# Sheet1.net
KiCad netlist of a schematic drawn in Altium Designer
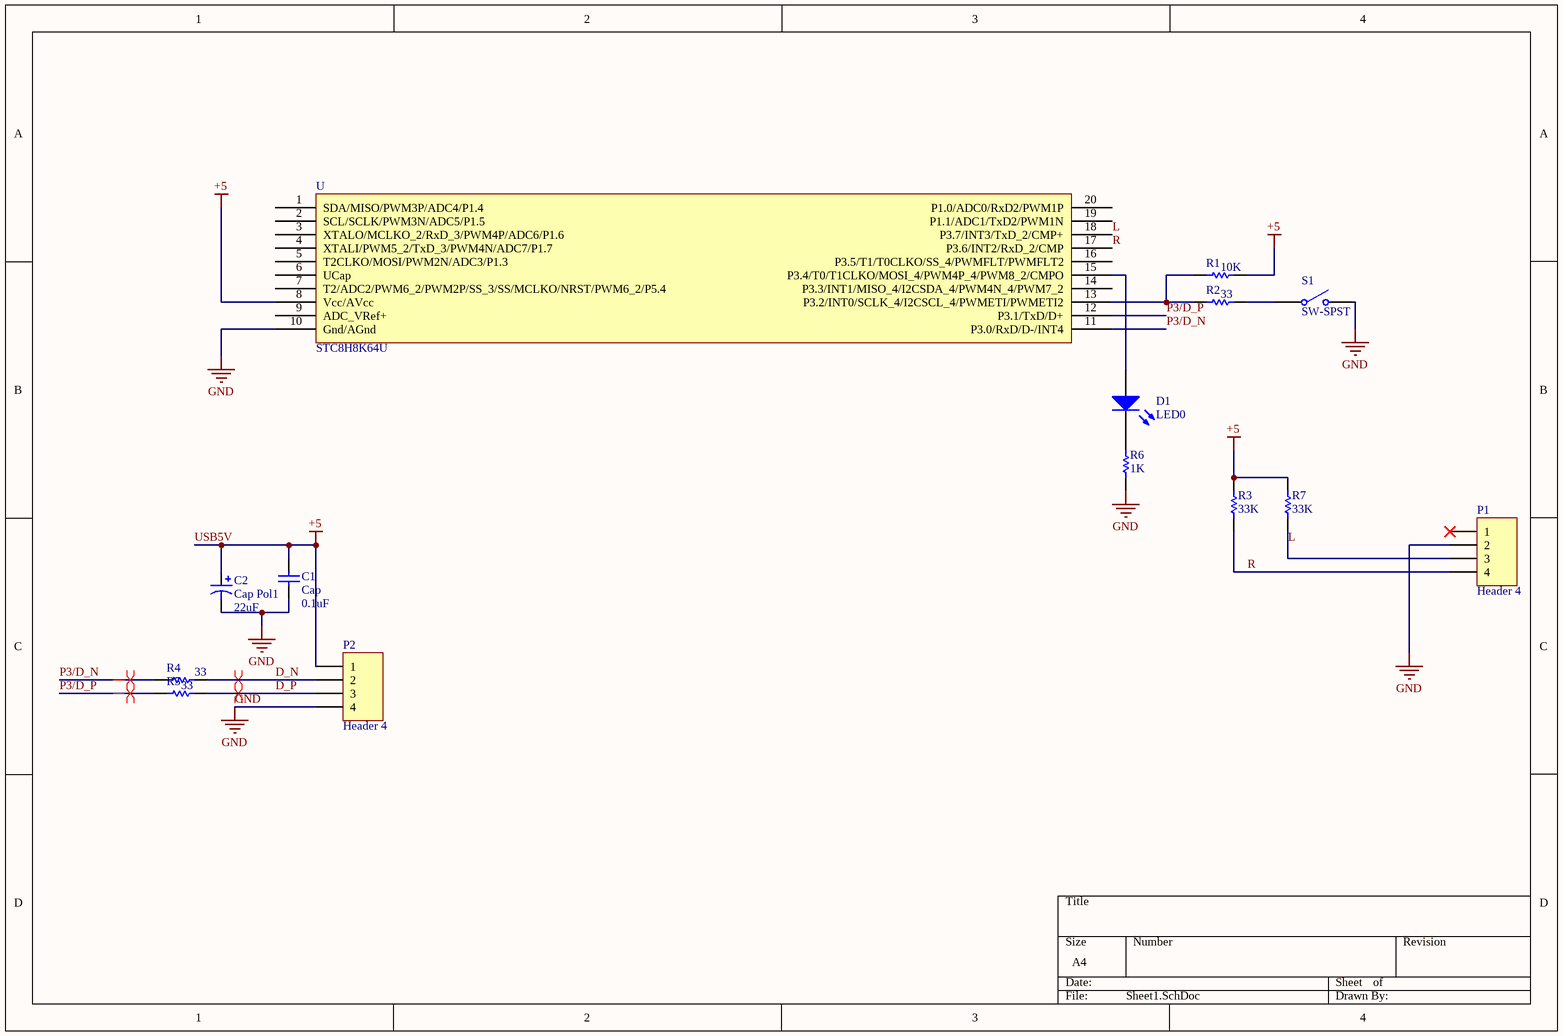
[diagram p0: Sheet1.SchDoc]

(export (version "E")
  (design (tool "Eeschema 10.0.6"))
  (components
    (comp (ref "C1")
      (value "Cap")
      (footprint "1608(0603)_C")
      (description "Capacitor")
      (fields (field (name "ALTIUM_VALUE") "0.1uF") (field (name "PUBLISHER") "Altium Limited"))
      (libsource (lib "Miscellaneous Devices") (part "Cap"))
    )
    (comp (ref "C2")
      (value "Cap Pol1")
      (footprint "1608(0603)_C")
      (description "Polarized Capacitor (Radial)")
      (fields (field (name "ALTIUM_VALUE") "22uF") (field (name "PUBLISHER") "Altium Limited"))
      (libsource (lib "Miscellaneous Devices") (part "Cap Pol1"))
    )
    (comp (ref "D1")
      (value "LED0")
      (footprint "1608(0603)_R")
      (description "Typical INFRARED GaAs LED")
      (fields (field (name "PUBLISHER") "Altium Limited"))
      (libsource (lib "Miscellaneous Devices") (part "LED0"))
    )
    (comp (ref "P1")
      (value "Header 4")
      (footprint "PJ-313D")
      (description "Header, 4-Pin")
      (fields (field (name "PUBLISHER") "Altium Limited"))
      (libsource (lib "Miscellaneous Connectors") (part "Header 4"))
    )
    (comp (ref "P2")
      (value "Header 4")
      (footprint "USB-A-DIP")
      (description "Header, 4-Pin")
      (fields (field (name "PUBLISHER") "Altium Limited"))
      (libsource (lib "Miscellaneous Connectors") (part "Header 4"))
    )
    (comp (ref "R1")
      (value "10K")
      (footprint "1608(0603)_R")
      (description "Resistor")
      (fields (field (name "Comment") "Res1") (field (name "PUBLISHER") "Altium Limited"))
      (libsource (lib "Miscellaneous Devices") (part "Res1"))
    )
    (comp (ref "R2")
      (value "33")
      (footprint "1608(0603)_R")
      (description "Resistor")
      (fields (field (name "Comment") "Res1") (field (name "PUBLISHER") "Altium Limited"))
      (libsource (lib "Miscellaneous Devices") (part "Res1"))
    )
    (comp (ref "R3")
      (value "33K")
      (footprint "1608(0603)_R")
      (description "Resistor")
      (fields (field (name "Comment") "Res1") (field (name "PUBLISHER") "Altium Limited"))
      (libsource (lib "Miscellaneous Devices") (part "Res1"))
    )
    (comp (ref "R4")
      (value "33")
      (footprint "1608(0603)_R")
      (description "Resistor")
      (fields (field (name "Comment") "Res1") (field (name "PUBLISHER") "Altium Limited"))
      (libsource (lib "Miscellaneous Devices") (part "Res1"))
    )
    (comp (ref "R5")
      (value "33")
      (footprint "1608(0603)_R")
      (description "Resistor")
      (fields (field (name "Comment") "Res1") (field (name "PUBLISHER") "Altium Limited"))
      (libsource (lib "Miscellaneous Devices") (part "Res1"))
    )
    (comp (ref "R6")
      (value "1K")
      (footprint "1608(0603)_R")
      (description "Resistor")
      (fields (field (name "Comment") "Res1") (field (name "PUBLISHER") "Altium Limited"))
      (libsource (lib "Miscellaneous Devices") (part "Res1"))
    )
    (comp (ref "R7")
      (value "33K")
      (footprint "1608(0603)_R")
      (description "Resistor")
      (fields (field (name "Comment") "Res1") (field (name "PUBLISHER") "Altium Limited"))
      (libsource (lib "Miscellaneous Devices") (part "Res1"))
    )
    (comp (ref "S1")
      (value "SW-SPST")
      (footprint "SWITCH2 3*6*2.5")
      (description "Single-Pole, Single-Throw Switch")
      (fields (field (name "PUBLISHER") "Altium Limited"))
      (libsource (lib "Miscellaneous Devices") (part "SW-SPST"))
    )
    (comp (ref "U")
      (value "STC8H8K64U")
      (footprint "TSOP65P640X120-20N")
      (libsource (lib "STC8H8K64U-45I-TSSOP20") (part "STC8H8K64U"))
    )
  )
  (nets
    (net (code "1") (name "+5") (class "Default")
      (node (ref "C1") (pin "2") (pinfunction "2_2") (pintype "passive"))
      (node (ref "C2") (pin "1") (pinfunction "1_1") (pintype "passive"))
      (node (ref "P2") (pin "1") (pinfunction "1_1") (pintype "passive"))
      (node (ref "R1") (pin "1") (pinfunction "1_1") (pintype "passive"))
      (node (ref "R3") (pin "1") (pinfunction "1_1") (pintype "passive"))
      (node (ref "R7") (pin "1") (pinfunction "1_1") (pintype "passive"))
      (node (ref "U") (pin "8") (pinfunction "Vcc/AVcc_8") (pintype "passive"))
    )
    (net (code "2") (name "/D_N") (class "Default")
      (node (ref "P2") (pin "2") (pinfunction "2_2") (pintype "passive"))
      (node (ref "R4") (pin "1") (pinfunction "1_1") (pintype "passive"))
    )
    (net (code "3") (name "/D_P") (class "Default")
      (node (ref "P2") (pin "3") (pinfunction "3_3") (pintype "passive"))
      (node (ref "R5") (pin "1") (pinfunction "1_1") (pintype "passive"))
    )
    (net (code "4") (name "/L") (class "Default")
      (node (ref "P1") (pin "3") (pinfunction "3_3") (pintype "passive"))
      (node (ref "R7") (pin "2") (pinfunction "2_2") (pintype "passive"))
      (node (ref "U") (pin "18") (pinfunction "P3.7/INT3/TxD_2/CMP+_18") (pintype "passive"))
    )
    (net (code "5") (name "/P3{slash}D_N") (class "Default")
      (node (ref "R4") (pin "2") (pinfunction "2_2") (pintype "passive"))
      (node (ref "U") (pin "11") (pinfunction "P3.0/RxD/D-/INT4_11") (pintype "passive"))
    )
    (net (code "6") (name "/P3{slash}D_P") (class "Default")
      (node (ref "R5") (pin "2") (pinfunction "2_2") (pintype "passive"))
      (node (ref "U") (pin "12") (pinfunction "P3.1/TxD/D+_12") (pintype "passive"))
    )
    (net (code "7") (name "/R") (class "Default")
      (node (ref "P1") (pin "4") (pinfunction "4_4") (pintype "passive"))
      (node (ref "R3") (pin "2") (pinfunction "2_2") (pintype "passive"))
      (node (ref "U") (pin "17") (pinfunction "P3.6/INT2/RxD_2/CMP_17") (pintype "passive"))
    )
    (net (code "8") (name "GND") (class "Default")
      (node (ref "C1") (pin "1") (pinfunction "1_1") (pintype "passive"))
      (node (ref "C2") (pin "2") (pinfunction "2_2") (pintype "passive"))
      (node (ref "P1") (pin "2") (pinfunction "2_2") (pintype "passive"))
      (node (ref "P2") (pin "4") (pinfunction "4_4") (pintype "passive"))
      (node (ref "R6") (pin "2") (pinfunction "2_2") (pintype "passive"))
      (node (ref "S1") (pin "2") (pinfunction "NO_2") (pintype "passive"))
      (node (ref "U") (pin "10") (pinfunction "Gnd/AGnd_10") (pintype "passive"))
    )
    (net (code "9") (name "Net-(D1-A)") (class "Default")
      (node (ref "D1") (pin "1") (pinfunction "A_1") (pintype "passive"))
      (node (ref "U") (pin "15") (pinfunction "P3.4/T0/T1CLKO/MOSI_4/PWM4P_4/PWM8_2/CMPO_15") (pintype "passive"))
    )
    (net (code "10") (name "Net-(D1-K)") (class "Default")
      (node (ref "D1") (pin "2") (pinfunction "K_2") (pintype "passive"))
      (node (ref "R6") (pin "1") (pinfunction "1_1") (pintype "passive"))
    )
    (net (code "11") (name "Net-(S1-COMMON)") (class "Default")
      (node (ref "R2") (pin "1") (pinfunction "1_1") (pintype "passive"))
      (node (ref "S1") (pin "1") (pinfunction "COMMON_1") (pintype "passive"))
    )
    (net (code "12") (name "Net-(U-P3.2{slash}INT0{slash}SCLK_4{slash}I2CSCL_4{slash}PWMETI{slash}PWMETI2)") (class "Default")
      (node (ref "R1") (pin "2") (pinfunction "2_2") (pintype "passive"))
      (node (ref "R2") (pin "2") (pinfunction "2_2") (pintype "passive"))
      (node (ref "U") (pin "13") (pinfunction "P3.2/INT0/SCLK_4/I2CSCL_4/PWMETI/PWMETI2_13") (pintype "passive"))
    )
    (net (code "13") (name "unconnected-(P1-Pad1)") (class "Default")
      (node (ref "P1") (pin "1") (pinfunction "1_1") (pintype "passive+no_connect"))
    )
    (net (code "14") (name "unconnected-(U-ADC_VRef+-Pad9)") (class "Default")
      (node (ref "U") (pin "9") (pinfunction "ADC_VRef+_9") (pintype "passive"))
    )
    (net (code "15") (name "unconnected-(U-P1.0{slash}ADC0{slash}RxD2{slash}PWM1P-Pad20)") (class "Default")
      (node (ref "U") (pin "20") (pinfunction "P1.0/ADC0/RxD2/PWM1P_20") (pintype "passive"))
    )
    (net (code "16") (name "unconnected-(U-P1.1{slash}ADC1{slash}TxD2{slash}PWM1N-Pad19)") (class "Default")
      (node (ref "U") (pin "19") (pinfunction "P1.1/ADC1/TxD2/PWM1N_19") (pintype "passive"))
    )
    (net (code "17") (name "unconnected-(U-P3.3{slash}INT1{slash}MISO_4{slash}I2CSDA_4{slash}PWM4N_4{slash}PWM7_2-Pad14)") (class "Default")
      (node (ref "U") (pin "14") (pinfunction "P3.3/INT1/MISO_4/I2CSDA_4/PWM4N_4/PWM7_2_14") (pintype "passive"))
    )
    (net (code "18") (name "unconnected-(U-P3.5{slash}T1{slash}T0CLKO{slash}SS_4{slash}PWMFLT{slash}PWMFLT2-Pad16)") (class "Default")
      (node (ref "U") (pin "16") (pinfunction "P3.5/T1/T0CLKO/SS_4/PWMFLT/PWMFLT2_16") (pintype "passive"))
    )
    (net (code "19") (name "unconnected-(U-SCL{slash}SCLK{slash}PWM3N{slash}ADC5{slash}P1.5-Pad2)") (class "Default")
      (node (ref "U") (pin "2") (pinfunction "SCL/SCLK/PWM3N/ADC5/P1.5_2") (pintype "passive"))
    )
    (net (code "20") (name "unconnected-(U-SDA{slash}MISO{slash}PWM3P{slash}ADC4{slash}P1.4-Pad1)") (class "Default")
      (node (ref "U") (pin "1") (pinfunction "SDA/MISO/PWM3P/ADC4/P1.4_1") (pintype "passive"))
    )
    (net (code "21") (name "unconnected-(U-T2CLKO{slash}MOSI{slash}PWM2N{slash}ADC3{slash}P1.3-Pad5)") (class "Default")
      (node (ref "U") (pin "5") (pinfunction "T2CLKO/MOSI/PWM2N/ADC3/P1.3_5") (pintype "passive"))
    )
    (net (code "22") (name "unconnected-(U-T2{slash}ADC2{slash}PWM6_2{slash}PWM2P{slash}SS_3{slash}SS{slash}MCLKO{slash}NRST{slash}PWM6_2{slash}P5.4-Pad7)") (class "Default")
      (node (ref "U") (pin "7") (pinfunction "T2/ADC2/PWM6_2/PWM2P/SS_3/SS/MCLKO/NRST/PWM6_2/P5.4_7") (pintype "passive"))
    )
    (net (code "23") (name "unconnected-(U-UCap-Pad6)") (class "Default")
      (node (ref "U") (pin "6") (pinfunction "UCap_6") (pintype "passive"))
    )
    (net (code "24") (name "unconnected-(U-XTALI{slash}PWM5_2{slash}TxD_3{slash}PWM4N{slash}ADC7{slash}P1.7-Pad4)") (class "Default")
      (node (ref "U") (pin "4") (pinfunction "XTALI/PWM5_2/TxD_3/PWM4N/ADC7/P1.7_4") (pintype "passive"))
    )
    (net (code "25") (name "unconnected-(U-XTALO{slash}MCLKO_2{slash}RxD_3{slash}PWM4P{slash}ADC6{slash}P1.6-Pad3)") (class "Default")
      (node (ref "U") (pin "3") (pinfunction "XTALO/MCLKO_2/RxD_3/PWM4P/ADC6/P1.6_3") (pintype "passive"))
    )
  )
)
